# OttoPi06a-RPi3AHAT.net
KiCad netlist of a schematic drawn in EAGLE
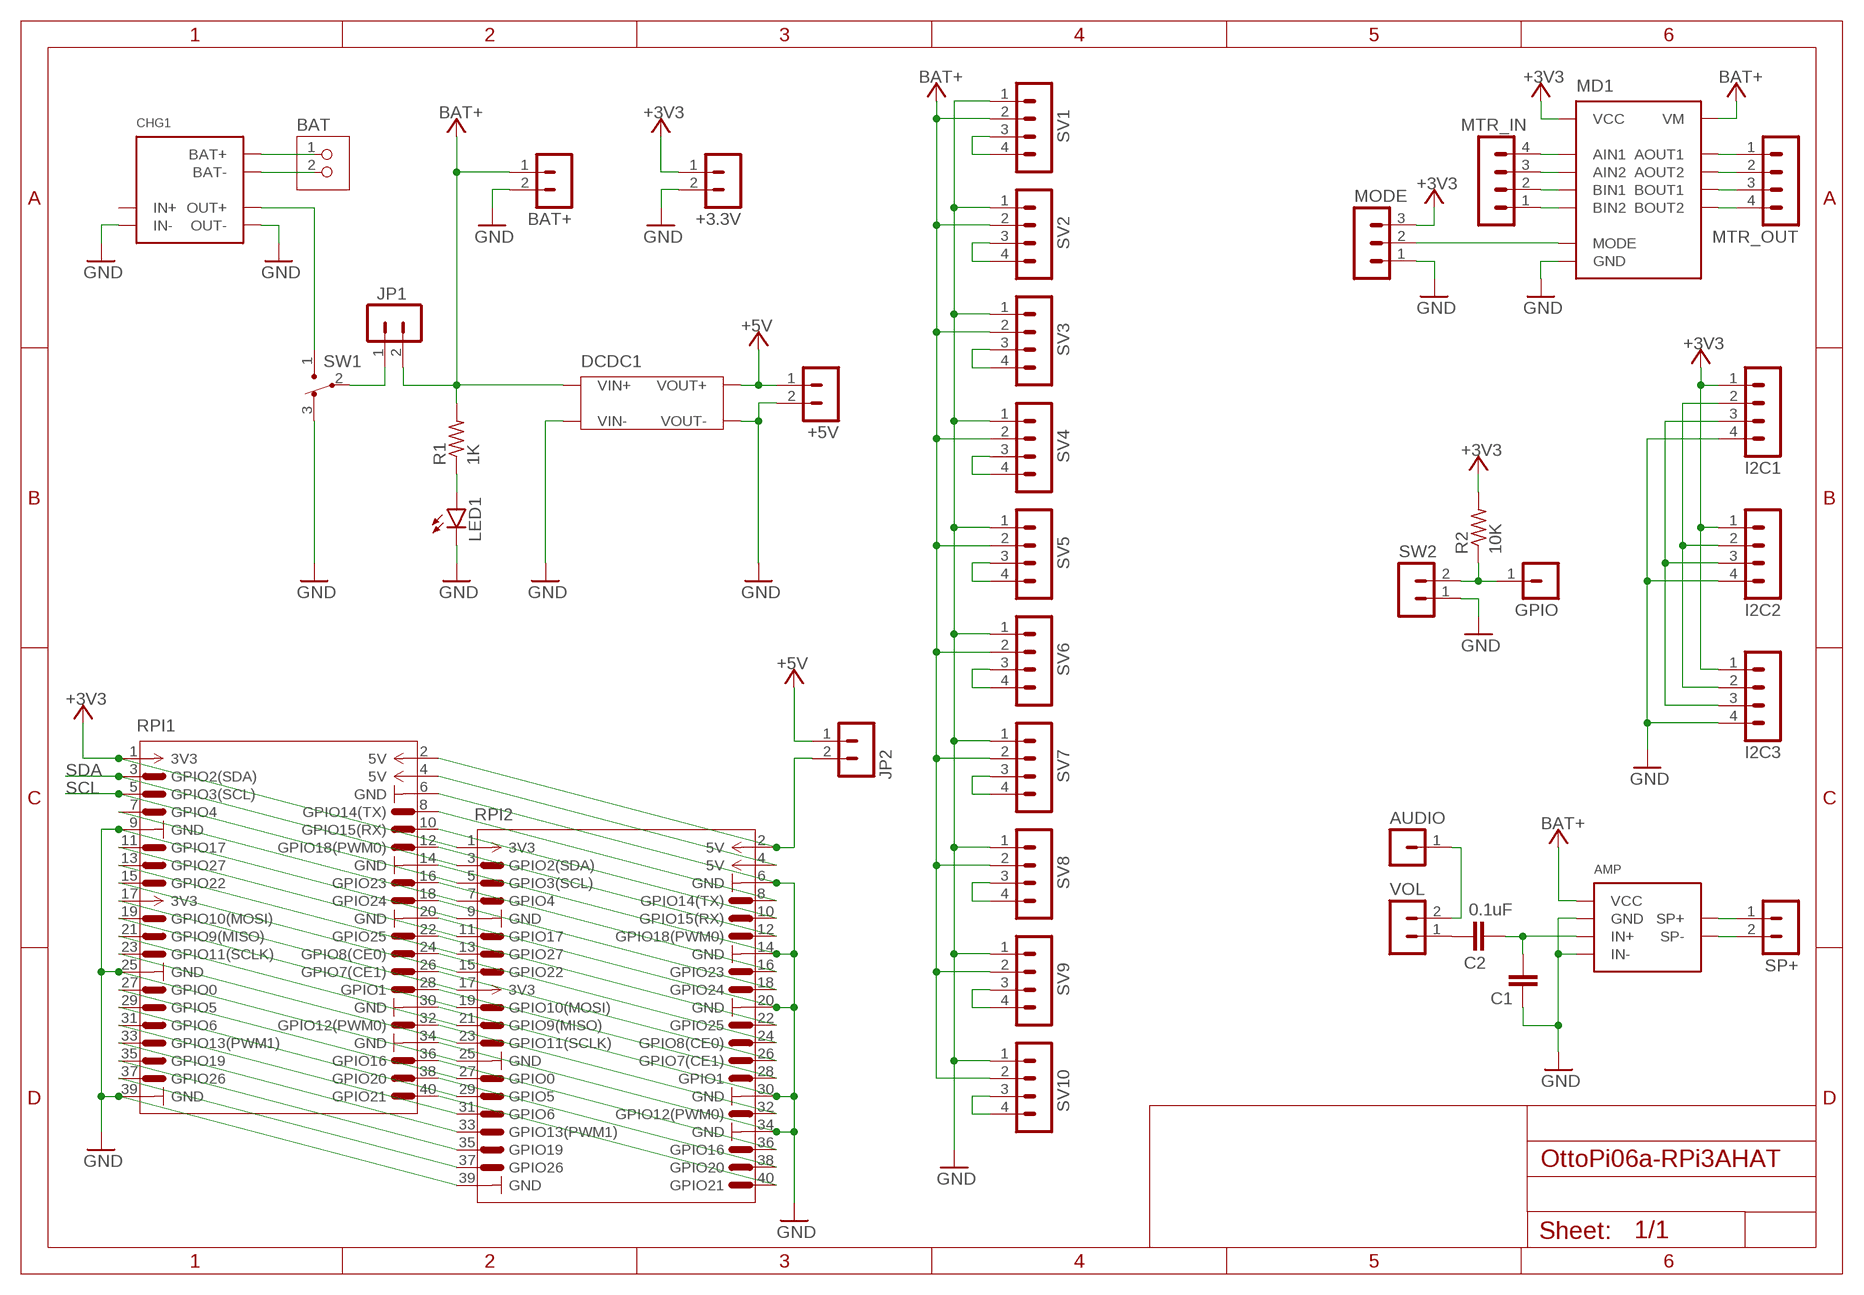
[diagram p0: schematic, sheet 1]

(export (version "E")
  (design (tool "Eeschema 10.0.6"))
  (components
    (comp (ref "+3.3V")
      (value "PINHEAD-MA02-1")
      (footprint "eagle-import:PINHEAD-MA02-1")
      (libsource (lib "eagle-import") (part "PINHEAD-MA02-1"))
    )
    (comp (ref "+5V")
      (value "PINHEAD-MA02-1")
      (footprint "eagle-import:PINHEAD-MA02-1")
      (libsource (lib "eagle-import") (part "PINHEAD-MA02-1"))
    )
    (comp (ref "AMP")
      (value "PAM8012MOD")
      (footprint "eagle-import:PAM8012MOD-A")
      (libsource (lib "eagle-import") (part "PAM8012MOD"))
    )
    (comp (ref "AUDIO")
      (value "PINHEAD-MA01-1")
      (footprint "eagle-import:PINHEAD-MA01-1")
      (libsource (lib "eagle-import") (part "PINHEAD-MA01-1"))
    )
    (comp (ref "BAT")
      (value "JST-PH2")
      (footprint "eagle-import:JST-PH2")
      (libsource (lib "eagle-import") (part "JST-PH2"))
    )
    (comp (ref "BAT+")
      (value "PINHEAD-MA02-1")
      (footprint "eagle-import:PINHEAD-MA02-1")
      (libsource (lib "eagle-import") (part "PINHEAD-MA02-1"))
    )
    (comp (ref "C1")
      (value "C-EU025-024X044")
      (footprint "eagle-import:C025-024X044")
      (libsource (lib "eagle-import") (part "C-EU025-024X044"))
    )
    (comp (ref "C2")
      (value "0.1uF")
      (footprint "eagle-import:C025-024X044")
      (libsource (lib "eagle-import") (part "C-EU025-024X044"))
    )
    (comp (ref "CHG1")
      (value "TP4056MOD1")
      (footprint "eagle-import:TP4056MOD1")
      (libsource (lib "eagle-import") (part "TP4056MOD1"))
    )
    (comp (ref "DCDC1")
      (value "DCDC-MT3608-MODUSB")
      (footprint "eagle-import:DCDC-MT3608-MOD2-USB")
      (libsource (lib "eagle-import") (part "DCDC-MT3608-MODUSB"))
    )
    (comp (ref "GPIO")
      (value "PINHEAD-MA01-1")
      (footprint "eagle-import:PINHEAD-MA01-1")
      (libsource (lib "eagle-import") (part "PINHEAD-MA01-1"))
    )
    (comp (ref "I2C1")
      (value "PINHEAD-MA04-1")
      (footprint "eagle-import:PINHEAD-MA04-1")
      (libsource (lib "eagle-import") (part "PINHEAD-MA04-1"))
    )
    (comp (ref "I2C2")
      (value "PINHEAD-MA04-1")
      (footprint "eagle-import:PINHEAD-MA04-1")
      (libsource (lib "eagle-import") (part "PINHEAD-MA04-1"))
    )
    (comp (ref "I2C3")
      (value "PINHEAD-MA04-1")
      (footprint "eagle-import:PINHEAD-MA04-1")
      (libsource (lib "eagle-import") (part "PINHEAD-MA04-1"))
    )
    (comp (ref "JP1")
      (value "PINHEAD-MA02-1")
      (footprint "eagle-import:PINHEAD-MA02-1")
      (libsource (lib "eagle-import") (part "PINHEAD-MA02-1"))
    )
    (comp (ref "JP2")
      (value "PINHEAD-MA02-1")
      (footprint "eagle-import:PINHEAD-MA02-1")
      (libsource (lib "eagle-import") (part "PINHEAD-MA02-1"))
    )
    (comp (ref "LED1")
      (value "LED3MM")
      (footprint "eagle-import:LED3MM")
      (libsource (lib "eagle-import") (part "LED3MM"))
    )
    (comp (ref "MD1")
      (value "DRV8835MOD")
      (footprint "eagle-import:DRV8835MOD")
      (libsource (lib "eagle-import") (part "DRV8835MOD"))
    )
    (comp (ref "MODE")
      (value "PINHEAD-MA03-1")
      (footprint "eagle-import:PINHEAD-MA03-1")
      (libsource (lib "eagle-import") (part "PINHEAD-MA03-1"))
    )
    (comp (ref "MTR_IN")
      (value "PINHEAD-MA04-1")
      (footprint "eagle-import:PINHEAD-MA04-1")
      (libsource (lib "eagle-import") (part "PINHEAD-MA04-1"))
    )
    (comp (ref "MTR_OUT")
      (value "PINHEAD-MA04-1")
      (footprint "eagle-import:PINHEAD-MA04-1")
      (libsource (lib "eagle-import") (part "PINHEAD-MA04-1"))
    )
    (comp (ref "R1")
      (value "1K")
      (footprint "eagle-import:0204_7")
      (libsource (lib "eagle-import") (part "R-US_0204/7"))
    )
    (comp (ref "R2")
      (value "10K")
      (footprint "eagle-import:0204_7")
      (libsource (lib "eagle-import") (part "R-US_0204/7"))
    )
    (comp (ref "RPI1")
      (value "RPI-PIN")
      (footprint "eagle-import:RPI-PIN")
      (libsource (lib "eagle-import") (part "RPI-PIN"))
    )
    (comp (ref "RPI2")
      (value "RPI-PIN")
      (footprint "eagle-import:RPI-PIN")
      (libsource (lib "eagle-import") (part "RPI-PIN"))
    )
    (comp (ref "SP+")
      (value "PINHEAD-MA02-1")
      (footprint "eagle-import:PINHEAD-MA02-1")
      (libsource (lib "eagle-import") (part "PINHEAD-MA02-1"))
    )
    (comp (ref "SV1")
      (value "PINHEAD-MA04-1")
      (footprint "eagle-import:PINHEAD-MA04-1")
      (libsource (lib "eagle-import") (part "PINHEAD-MA04-1"))
    )
    (comp (ref "SV2")
      (value "PINHEAD-MA04-1")
      (footprint "eagle-import:PINHEAD-MA04-1")
      (libsource (lib "eagle-import") (part "PINHEAD-MA04-1"))
    )
    (comp (ref "SV3")
      (value "PINHEAD-MA04-1")
      (footprint "eagle-import:PINHEAD-MA04-1")
      (libsource (lib "eagle-import") (part "PINHEAD-MA04-1"))
    )
    (comp (ref "SV4")
      (value "PINHEAD-MA04-1")
      (footprint "eagle-import:PINHEAD-MA04-1")
      (libsource (lib "eagle-import") (part "PINHEAD-MA04-1"))
    )
    (comp (ref "SV5")
      (value "PINHEAD-MA04-1")
      (footprint "eagle-import:PINHEAD-MA04-1")
      (libsource (lib "eagle-import") (part "PINHEAD-MA04-1"))
    )
    (comp (ref "SV6")
      (value "PINHEAD-MA04-1")
      (footprint "eagle-import:PINHEAD-MA04-1")
      (libsource (lib "eagle-import") (part "PINHEAD-MA04-1"))
    )
    (comp (ref "SV7")
      (value "PINHEAD-MA04-1")
      (footprint "eagle-import:PINHEAD-MA04-1")
      (libsource (lib "eagle-import") (part "PINHEAD-MA04-1"))
    )
    (comp (ref "SV8")
      (value "PINHEAD-MA04-1")
      (footprint "eagle-import:PINHEAD-MA04-1")
      (libsource (lib "eagle-import") (part "PINHEAD-MA04-1"))
    )
    (comp (ref "SV9")
      (value "PINHEAD-MA04-1")
      (footprint "eagle-import:PINHEAD-MA04-1")
      (libsource (lib "eagle-import") (part "PINHEAD-MA04-1"))
    )
    (comp (ref "SV10")
      (value "PINHEAD-MA04-1")
      (footprint "eagle-import:PINHEAD-MA04-1")
      (libsource (lib "eagle-import") (part "PINHEAD-MA04-1"))
    )
    (comp (ref "SW1")
      (value "SW3-1")
      (footprint "eagle-import:SW3-1")
      (fields (field (name "MF") "HiLetgo"))
      (libsource (lib "eagle-import") (part "SW3-1"))
    )
    (comp (ref "SW2")
      (value "PINHEAD-MA02-1")
      (footprint "eagle-import:PINHEAD-MA02-1")
      (libsource (lib "eagle-import") (part "PINHEAD-MA02-1"))
    )
    (comp (ref "VOL")
      (value "PINHEAD-MA02-1")
      (footprint "eagle-import:PINHEAD-MA02-1")
      (libsource (lib "eagle-import") (part "PINHEAD-MA02-1"))
    )
  )
  (nets
    (net (code "1") (name "+3V3") (class "Default")
      (node (ref "+3.3V") (pin "1") (pinfunction "1_1") (pintype "passive"))
      (node (ref "I2C1") (pin "1") (pinfunction "1_1") (pintype "passive"))
      (node (ref "I2C2") (pin "1") (pinfunction "1_1") (pintype "passive"))
      (node (ref "I2C3") (pin "1") (pinfunction "1_1") (pintype "passive"))
      (node (ref "MD1") (pin "VCC") (pinfunction "VCC_VCC") (pintype "input"))
      (node (ref "MODE") (pin "3") (pinfunction "3_3") (pintype "passive"))
      (node (ref "R2") (pin "2") (pinfunction "2_2") (pintype "passive"))
      (node (ref "RPI1") (pin "1") (pinfunction "3V3_1") (pintype "passive"))
      (node (ref "RPI2") (pin "1") (pinfunction "3V3_1") (pintype "passive"))
    )
    (net (code "2") (name "+5V") (class "Default")
      (node (ref "+5V") (pin "1") (pinfunction "1_1") (pintype "passive"))
      (node (ref "DCDC1") (pin "VOUT+") (pinfunction "VOUT+_VOUT+") (pintype "power_in"))
      (node (ref "JP2") (pin "1") (pinfunction "1_1") (pintype "passive"))
    )
    (net (code "3") (name "/SCL") (class "Default")
      (node (ref "I2C1") (pin "3") (pinfunction "3_3") (pintype "passive"))
      (node (ref "I2C2") (pin "3") (pinfunction "3_3") (pintype "passive"))
      (node (ref "I2C3") (pin "3") (pinfunction "3_3") (pintype "passive"))
      (node (ref "RPI1") (pin "5") (pinfunction "GPIO3(SCL)_5") (pintype "passive"))
      (node (ref "RPI2") (pin "5") (pinfunction "GPIO3(SCL)_5") (pintype "passive"))
    )
    (net (code "4") (name "/SDA") (class "Default")
      (node (ref "I2C1") (pin "2") (pinfunction "2_2") (pintype "passive"))
      (node (ref "I2C2") (pin "2") (pinfunction "2_2") (pintype "passive"))
      (node (ref "I2C3") (pin "2") (pinfunction "2_2") (pintype "passive"))
      (node (ref "RPI1") (pin "3") (pinfunction "GPIO2(SDA)_3") (pintype "passive"))
      (node (ref "RPI2") (pin "3") (pinfunction "GPIO2(SDA)_3") (pintype "passive"))
    )
    (net (code "5") (name "BAT+") (class "Default")
      (node (ref "AMP") (pin "V+") (pinfunction "VCC_V+") (pintype "passive"))
      (node (ref "BAT+") (pin "1") (pinfunction "1_1") (pintype "passive"))
      (node (ref "DCDC1") (pin "VIN+") (pinfunction "VIN+_VIN+") (pintype "power_in"))
      (node (ref "JP1") (pin "2") (pinfunction "2_2") (pintype "passive"))
      (node (ref "MD1") (pin "VM") (pinfunction "VM_VM") (pintype "input"))
      (node (ref "R1") (pin "2") (pinfunction "2_2") (pintype "passive"))
      (node (ref "SV1") (pin "2") (pinfunction "2_2") (pintype "passive"))
      (node (ref "SV10") (pin "2") (pinfunction "2_2") (pintype "passive"))
      (node (ref "SV2") (pin "2") (pinfunction "2_2") (pintype "passive"))
      (node (ref "SV3") (pin "2") (pinfunction "2_2") (pintype "passive"))
      (node (ref "SV4") (pin "2") (pinfunction "2_2") (pintype "passive"))
      (node (ref "SV5") (pin "2") (pinfunction "2_2") (pintype "passive"))
      (node (ref "SV6") (pin "2") (pinfunction "2_2") (pintype "passive"))
      (node (ref "SV7") (pin "2") (pinfunction "2_2") (pintype "passive"))
      (node (ref "SV8") (pin "2") (pinfunction "2_2") (pintype "passive"))
      (node (ref "SV9") (pin "2") (pinfunction "2_2") (pintype "passive"))
    )
    (net (code "6") (name "GND") (class "Default")
      (node (ref "+3.3V") (pin "2") (pinfunction "2_2") (pintype "passive"))
      (node (ref "+5V") (pin "2") (pinfunction "2_2") (pintype "passive"))
      (node (ref "AMP") (pin "GND") (pinfunction "GND_GND") (pintype "passive"))
      (node (ref "AMP") (pin "IN-") (pinfunction "IN-_IN-") (pintype "input"))
      (node (ref "BAT+") (pin "2") (pinfunction "2_2") (pintype "passive"))
      (node (ref "C1") (pin "1") (pinfunction "1_1") (pintype "passive"))
      (node (ref "CHG1") (pin "IN-") (pinfunction "IN-_IN-") (pintype "passive"))
      (node (ref "CHG1") (pin "OUT-") (pinfunction "OUT-_OUT-") (pintype "passive"))
      (node (ref "DCDC1") (pin "VIN-") (pinfunction "VIN-_VIN-") (pintype "power_in"))
      (node (ref "DCDC1") (pin "VOUT-") (pinfunction "VOUT-_VOUT-") (pintype "power_in"))
      (node (ref "I2C1") (pin "4") (pinfunction "4_4") (pintype "passive"))
      (node (ref "I2C2") (pin "4") (pinfunction "4_4") (pintype "passive"))
      (node (ref "I2C3") (pin "4") (pinfunction "4_4") (pintype "passive"))
      (node (ref "LED1") (pin "K") (pinfunction "C_K") (pintype "passive"))
      (node (ref "MD1") (pin "GND") (pinfunction "GND_GND") (pintype "power_in"))
      (node (ref "MODE") (pin "1") (pinfunction "1_1") (pintype "passive"))
      (node (ref "RPI1") (pin "14") (pinfunction "GND_14") (pintype "passive"))
      (node (ref "RPI1") (pin "20") (pinfunction "GND_20") (pintype "passive"))
      (node (ref "RPI1") (pin "25") (pinfunction "GND_25") (pintype "passive"))
      (node (ref "RPI1") (pin "30") (pinfunction "GND_30") (pintype "passive"))
      (node (ref "RPI1") (pin "34") (pinfunction "GND_34") (pintype "passive"))
      (node (ref "RPI1") (pin "39") (pinfunction "GND_39") (pintype "passive"))
      (node (ref "RPI1") (pin "6") (pinfunction "GND_6") (pintype "passive"))
      (node (ref "RPI1") (pin "9") (pinfunction "GND_9") (pintype "passive"))
      (node (ref "RPI2") (pin "14") (pinfunction "GND_14") (pintype "passive"))
      (node (ref "RPI2") (pin "20") (pinfunction "GND_20") (pintype "passive"))
      (node (ref "RPI2") (pin "25") (pinfunction "GND_25") (pintype "passive"))
      (node (ref "RPI2") (pin "30") (pinfunction "GND_30") (pintype "passive"))
      (node (ref "RPI2") (pin "34") (pinfunction "GND_34") (pintype "passive"))
      (node (ref "RPI2") (pin "39") (pinfunction "GND_39") (pintype "passive"))
      (node (ref "RPI2") (pin "6") (pinfunction "GND_6") (pintype "passive"))
      (node (ref "RPI2") (pin "9") (pinfunction "GND_9") (pintype "passive"))
      (node (ref "SV1") (pin "1") (pinfunction "1_1") (pintype "passive"))
      (node (ref "SV10") (pin "1") (pinfunction "1_1") (pintype "passive"))
      (node (ref "SV2") (pin "1") (pinfunction "1_1") (pintype "passive"))
      (node (ref "SV3") (pin "1") (pinfunction "1_1") (pintype "passive"))
      (node (ref "SV4") (pin "1") (pinfunction "1_1") (pintype "passive"))
      (node (ref "SV5") (pin "1") (pinfunction "1_1") (pintype "passive"))
      (node (ref "SV6") (pin "1") (pinfunction "1_1") (pintype "passive"))
      (node (ref "SV7") (pin "1") (pinfunction "1_1") (pintype "passive"))
      (node (ref "SV8") (pin "1") (pinfunction "1_1") (pintype "passive"))
      (node (ref "SV9") (pin "1") (pinfunction "1_1") (pintype "passive"))
      (node (ref "SW1") (pin "3") (pinfunction "3_3") (pintype "passive"))
      (node (ref "SW2") (pin "1") (pinfunction "1_1") (pintype "passive"))
    )
    (net (code "7") (name "Net-(AMP-PadIN+)") (class "Default")
      (node (ref "AMP") (pin "IN+") (pinfunction "IN+_IN+") (pintype "input"))
      (node (ref "C1") (pin "2") (pinfunction "2_2") (pintype "passive"))
      (node (ref "C2") (pin "1") (pinfunction "1_1") (pintype "passive"))
    )
    (net (code "8") (name "Net-(AMP-SP+)") (class "Default")
      (node (ref "AMP") (pin "SP+@1") (pinfunction "SP+_SP+@1") (pintype "output"))
      (node (ref "SP+") (pin "1") (pinfunction "1_1") (pintype "passive"))
    )
    (net (code "9") (name "Net-(AMP-SP-)") (class "Default")
      (node (ref "AMP") (pin "SP-@1") (pinfunction "SP-_SP-@1") (pintype "output"))
      (node (ref "SP+") (pin "2") (pinfunction "2_2") (pintype "passive"))
    )
    (net (code "10") (name "Net-(AUDIO-Pad1)") (class "Default")
      (node (ref "AUDIO") (pin "1") (pinfunction "1_1") (pintype "passive"))
      (node (ref "VOL") (pin "2") (pinfunction "2_2") (pintype "passive"))
    )
    (net (code "11") (name "Net-(BAT-Pad1)") (class "Default")
      (node (ref "BAT") (pin "1") (pinfunction "1_1") (pintype "passive"))
      (node (ref "CHG1") (pin "BAT+") (pinfunction "BAT+_BAT+") (pintype "passive"))
    )
    (net (code "12") (name "Net-(BAT-Pad2)") (class "Default")
      (node (ref "BAT") (pin "2") (pinfunction "2_2") (pintype "passive"))
      (node (ref "CHG1") (pin "BAT-") (pinfunction "BAT-_BAT-") (pintype "passive"))
    )
    (net (code "13") (name "Net-(C2-Pad2)") (class "Default")
      (node (ref "C2") (pin "2") (pinfunction "2_2") (pintype "passive"))
      (node (ref "VOL") (pin "1") (pinfunction "1_1") (pintype "passive"))
    )
    (net (code "14") (name "Net-(CHG1-PadOUT+)") (class "Default")
      (node (ref "CHG1") (pin "OUT+") (pinfunction "OUT+_OUT+") (pintype "passive"))
      (node (ref "SW1") (pin "1") (pinfunction "1_1") (pintype "passive"))
    )
    (net (code "15") (name "Net-(GPIO-Pad1)") (class "Default")
      (node (ref "GPIO") (pin "1") (pinfunction "1_1") (pintype "passive"))
      (node (ref "R2") (pin "1") (pinfunction "1_1") (pintype "passive"))
      (node (ref "SW2") (pin "2") (pinfunction "2_2") (pintype "passive"))
    )
    (net (code "16") (name "Net-(JP1-Pad1)") (class "Default")
      (node (ref "JP1") (pin "1") (pinfunction "1_1") (pintype "passive"))
      (node (ref "SW1") (pin "2") (pinfunction "2_2") (pintype "passive"))
    )
    (net (code "17") (name "Net-(JP2-Pad2)") (class "Default")
      (node (ref "JP2") (pin "2") (pinfunction "2_2") (pintype "passive"))
      (node (ref "RPI1") (pin "2") (pinfunction "5V_2") (pintype "passive"))
      (node (ref "RPI2") (pin "2") (pinfunction "5V_2") (pintype "passive"))
    )
    (net (code "18") (name "Net-(LED1-PadA)") (class "Default")
      (node (ref "LED1") (pin "A") (pinfunction "A_A") (pintype "passive"))
      (node (ref "R1") (pin "1") (pinfunction "1_1") (pintype "passive"))
    )
    (net (code "19") (name "Net-(MD1-PadAIN1)") (class "Default")
      (node (ref "MD1") (pin "AIN1") (pinfunction "AIN1_AIN1") (pintype "input"))
      (node (ref "MTR_IN") (pin "4") (pinfunction "4_4") (pintype "passive"))
    )
    (net (code "20") (name "Net-(MD1-PadAIN2)") (class "Default")
      (node (ref "MD1") (pin "AIN2") (pinfunction "AIN2_AIN2") (pintype "input"))
      (node (ref "MTR_IN") (pin "3") (pinfunction "3_3") (pintype "passive"))
    )
    (net (code "21") (name "Net-(MD1-PadAOUT1)") (class "Default")
      (node (ref "MD1") (pin "AOUT1") (pinfunction "AOUT1_AOUT1") (pintype "output"))
      (node (ref "MTR_OUT") (pin "1") (pinfunction "1_1") (pintype "passive"))
    )
    (net (code "22") (name "Net-(MD1-PadAOUT2)") (class "Default")
      (node (ref "MD1") (pin "AOUT2") (pinfunction "AOUT2_AOUT2") (pintype "output"))
      (node (ref "MTR_OUT") (pin "2") (pinfunction "2_2") (pintype "passive"))
    )
    (net (code "23") (name "Net-(MD1-PadBIN1)") (class "Default")
      (node (ref "MD1") (pin "BIN1") (pinfunction "BIN1_BIN1") (pintype "input"))
      (node (ref "MTR_IN") (pin "2") (pinfunction "2_2") (pintype "passive"))
    )
    (net (code "24") (name "Net-(MD1-PadBIN2)") (class "Default")
      (node (ref "MD1") (pin "BIN2") (pinfunction "BIN2_BIN2") (pintype "input"))
      (node (ref "MTR_IN") (pin "1") (pinfunction "1_1") (pintype "passive"))
    )
    (net (code "25") (name "Net-(MD1-PadBOUT1)") (class "Default")
      (node (ref "MD1") (pin "BOUT1") (pinfunction "BOUT1_BOUT1") (pintype "output"))
      (node (ref "MTR_OUT") (pin "3") (pinfunction "3_3") (pintype "passive"))
    )
    (net (code "26") (name "Net-(MD1-PadBOUT2)") (class "Default")
      (node (ref "MD1") (pin "BOUT2") (pinfunction "BOUT2_BOUT2") (pintype "output"))
      (node (ref "MTR_OUT") (pin "4") (pinfunction "4_4") (pintype "passive"))
    )
    (net (code "27") (name "Net-(MD1-PadMODE)") (class "Default")
      (node (ref "MD1") (pin "MODE") (pinfunction "MODE_MODE") (pintype "input"))
      (node (ref "MODE") (pin "2") (pinfunction "2_2") (pintype "passive"))
    )
    (net (code "28") (name "Net-(RPI1-3V3-Pad17)") (class "Default")
      (node (ref "RPI1") (pin "17") (pinfunction "3V3_17") (pintype "passive"))
      (node (ref "RPI2") (pin "17") (pinfunction "3V3_17") (pintype "passive"))
    )
    (net (code "29") (name "Net-(RPI1-5V-Pad4)") (class "Default")
      (node (ref "RPI1") (pin "4") (pinfunction "5V_4") (pintype "passive"))
      (node (ref "RPI2") (pin "4") (pinfunction "5V_4") (pintype "passive"))
    )
    (net (code "30") (name "Net-(RPI1-GPIO0)") (class "Default")
      (node (ref "RPI1") (pin "27") (pinfunction "GPIO0_27") (pintype "passive"))
      (node (ref "RPI2") (pin "27") (pinfunction "GPIO0_27") (pintype "passive"))
    )
    (net (code "31") (name "Net-(RPI1-GPIO1)") (class "Default")
      (node (ref "RPI1") (pin "28") (pinfunction "GPIO1_28") (pintype "passive"))
      (node (ref "RPI2") (pin "28") (pinfunction "GPIO1_28") (pintype "passive"))
    )
    (net (code "32") (name "Net-(RPI1-GPIO4)") (class "Default")
      (node (ref "RPI1") (pin "7") (pinfunction "GPIO4_7") (pintype "passive"))
      (node (ref "RPI2") (pin "7") (pinfunction "GPIO4_7") (pintype "passive"))
    )
    (net (code "33") (name "Net-(RPI1-GPIO5)") (class "Default")
      (node (ref "RPI1") (pin "29") (pinfunction "GPIO5_29") (pintype "passive"))
      (node (ref "RPI2") (pin "29") (pinfunction "GPIO5_29") (pintype "passive"))
    )
    (net (code "34") (name "Net-(RPI1-GPIO6)") (class "Default")
      (node (ref "RPI1") (pin "31") (pinfunction "GPIO6_31") (pintype "passive"))
      (node (ref "RPI2") (pin "31") (pinfunction "GPIO6_31") (pintype "passive"))
    )
    (net (code "35") (name "Net-(RPI1-GPIO7(CE1))") (class "Default")
      (node (ref "RPI1") (pin "26") (pinfunction "GPIO7(CE1)_26") (pintype "passive"))
      (node (ref "RPI2") (pin "26") (pinfunction "GPIO7(CE1)_26") (pintype "passive"))
    )
    (net (code "36") (name "Net-(RPI1-GPIO8(CE0))") (class "Default")
      (node (ref "RPI1") (pin "24") (pinfunction "GPIO8(CE0)_24") (pintype "passive"))
      (node (ref "RPI2") (pin "24") (pinfunction "GPIO8(CE0)_24") (pintype "passive"))
    )
    (net (code "37") (name "Net-(RPI1-GPIO9(MISO))") (class "Default")
      (node (ref "RPI1") (pin "21") (pinfunction "GPIO9(MISO)_21") (pintype "passive"))
      (node (ref "RPI2") (pin "21") (pinfunction "GPIO9(MISO)_21") (pintype "passive"))
    )
    (net (code "38") (name "Net-(RPI1-GPIO10(MOSI))") (class "Default")
      (node (ref "RPI1") (pin "19") (pinfunction "GPIO10(MOSI)_19") (pintype "passive"))
      (node (ref "RPI2") (pin "19") (pinfunction "GPIO10(MOSI)_19") (pintype "passive"))
    )
    (net (code "39") (name "Net-(RPI1-GPIO11(SCLK))") (class "Default")
      (node (ref "RPI1") (pin "23") (pinfunction "GPIO11(SCLK)_23") (pintype "passive"))
      (node (ref "RPI2") (pin "23") (pinfunction "GPIO11(SCLK)_23") (pintype "passive"))
    )
    (net (code "40") (name "Net-(RPI1-GPIO12(PWM0))") (class "Default")
      (node (ref "RPI1") (pin "32") (pinfunction "GPIO12(PWM0)_32") (pintype "passive"))
      (node (ref "RPI2") (pin "32") (pinfunction "GPIO12(PWM0)_32") (pintype "passive"))
    )
    (net (code "41") (name "Net-(RPI1-GPIO13(PWM1))") (class "Default")
      (node (ref "RPI1") (pin "33") (pinfunction "GPIO13(PWM1)_33") (pintype "passive"))
      (node (ref "RPI2") (pin "33") (pinfunction "GPIO13(PWM1)_33") (pintype "passive"))
    )
    (net (code "42") (name "Net-(RPI1-GPIO14(TX))") (class "Default")
      (node (ref "RPI1") (pin "8") (pinfunction "GPIO14(TX)_8") (pintype "passive"))
      (node (ref "RPI2") (pin "8") (pinfunction "GPIO14(TX)_8") (pintype "passive"))
    )
    (net (code "43") (name "Net-(RPI1-GPIO15(RX))") (class "Default")
      (node (ref "RPI1") (pin "10") (pinfunction "GPIO15(RX)_10") (pintype "passive"))
      (node (ref "RPI2") (pin "10") (pinfunction "GPIO15(RX)_10") (pintype "passive"))
    )
    (net (code "44") (name "Net-(RPI1-GPIO16)") (class "Default")
      (node (ref "RPI1") (pin "36") (pinfunction "GPIO16_36") (pintype "passive"))
      (node (ref "RPI2") (pin "36") (pinfunction "GPIO16_36") (pintype "passive"))
    )
    (net (code "45") (name "Net-(RPI1-GPIO17)") (class "Default")
      (node (ref "RPI1") (pin "11") (pinfunction "GPIO17_11") (pintype "passive"))
      (node (ref "RPI2") (pin "11") (pinfunction "GPIO17_11") (pintype "passive"))
    )
    (net (code "46") (name "Net-(RPI1-GPIO18(PWM0))") (class "Default")
      (node (ref "RPI1") (pin "12") (pinfunction "GPIO18(PWM0)_12") (pintype "passive"))
      (node (ref "RPI2") (pin "12") (pinfunction "GPIO18(PWM0)_12") (pintype "passive"))
    )
    (net (code "47") (name "Net-(RPI1-GPIO19)") (class "Default")
      (node (ref "RPI1") (pin "35") (pinfunction "GPIO19_35") (pintype "passive"))
      (node (ref "RPI2") (pin "35") (pinfunction "GPIO19_35") (pintype "passive"))
    )
    (net (code "48") (name "Net-(RPI1-GPIO20)") (class "Default")
      (node (ref "RPI1") (pin "38") (pinfunction "GPIO20_38") (pintype "passive"))
      (node (ref "RPI2") (pin "38") (pinfunction "GPIO20_38") (pintype "passive"))
    )
    (net (code "49") (name "Net-(RPI1-GPIO21)") (class "Default")
      (node (ref "RPI1") (pin "40") (pinfunction "GPIO21_40") (pintype "passive"))
      (node (ref "RPI2") (pin "40") (pinfunction "GPIO21_40") (pintype "passive"))
    )
    (net (code "50") (name "Net-(RPI1-GPIO22)") (class "Default")
      (node (ref "RPI1") (pin "15") (pinfunction "GPIO22_15") (pintype "passive"))
      (node (ref "RPI2") (pin "15") (pinfunction "GPIO22_15") (pintype "passive"))
    )
    (net (code "51") (name "Net-(RPI1-GPIO23)") (class "Default")
      (node (ref "RPI1") (pin "16") (pinfunction "GPIO23_16") (pintype "passive"))
      (node (ref "RPI2") (pin "16") (pinfunction "GPIO23_16") (pintype "passive"))
    )
    (net (code "52") (name "Net-(RPI1-GPIO24)") (class "Default")
      (node (ref "RPI1") (pin "18") (pinfunction "GPIO24_18") (pintype "passive"))
      (node (ref "RPI2") (pin "18") (pinfunction "GPIO24_18") (pintype "passive"))
    )
    (net (code "53") (name "Net-(RPI1-GPIO25)") (class "Default")
      (node (ref "RPI1") (pin "22") (pinfunction "GPIO25_22") (pintype "passive"))
      (node (ref "RPI2") (pin "22") (pinfunction "GPIO25_22") (pintype "passive"))
    )
    (net (code "54") (name "Net-(RPI1-GPIO26)") (class "Default")
      (node (ref "RPI1") (pin "37") (pinfunction "GPIO26_37") (pintype "passive"))
      (node (ref "RPI2") (pin "37") (pinfunction "GPIO26_37") (pintype "passive"))
    )
    (net (code "55") (name "Net-(RPI1-GPIO27)") (class "Default")
      (node (ref "RPI1") (pin "13") (pinfunction "GPIO27_13") (pintype "passive"))
      (node (ref "RPI2") (pin "13") (pinfunction "GPIO27_13") (pintype "passive"))
    )
    (net (code "56") (name "Net-(SV1-Pad3)") (class "Default")
      (node (ref "SV1") (pin "3") (pinfunction "3_3") (pintype "passive"))
      (node (ref "SV1") (pin "4") (pinfunction "4_4") (pintype "passive"))
    )
    (net (code "57") (name "Net-(SV2-Pad3)") (class "Default")
      (node (ref "SV2") (pin "3") (pinfunction "3_3") (pintype "passive"))
      (node (ref "SV2") (pin "4") (pinfunction "4_4") (pintype "passive"))
    )
    (net (code "58") (name "Net-(SV3-Pad3)") (class "Default")
      (node (ref "SV3") (pin "3") (pinfunction "3_3") (pintype "passive"))
      (node (ref "SV3") (pin "4") (pinfunction "4_4") (pintype "passive"))
    )
    (net (code "59") (name "Net-(SV4-Pad3)") (class "Default")
      (node (ref "SV4") (pin "3") (pinfunction "3_3") (pintype "passive"))
      (node (ref "SV4") (pin "4") (pinfunction "4_4") (pintype "passive"))
    )
    (net (code "60") (name "Net-(SV5-Pad3)") (class "Default")
      (node (ref "SV5") (pin "3") (pinfunction "3_3") (pintype "passive"))
      (node (ref "SV5") (pin "4") (pinfunction "4_4") (pintype "passive"))
    )
    (net (code "61") (name "Net-(SV6-Pad3)") (class "Default")
      (node (ref "SV6") (pin "3") (pinfunction "3_3") (pintype "passive"))
      (node (ref "SV6") (pin "4") (pinfunction "4_4") (pintype "passive"))
    )
    (net (code "62") (name "Net-(SV7-Pad3)") (class "Default")
      (node (ref "SV7") (pin "3") (pinfunction "3_3") (pintype "passive"))
      (node (ref "SV7") (pin "4") (pinfunction "4_4") (pintype "passive"))
    )
    (net (code "63") (name "Net-(SV8-Pad3)") (class "Default")
      (node (ref "SV8") (pin "3") (pinfunction "3_3") (pintype "passive"))
      (node (ref "SV8") (pin "4") (pinfunction "4_4") (pintype "passive"))
    )
    (net (code "64") (name "Net-(SV9-Pad3)") (class "Default")
      (node (ref "SV9") (pin "3") (pinfunction "3_3") (pintype "passive"))
      (node (ref "SV9") (pin "4") (pinfunction "4_4") (pintype "passive"))
    )
    (net (code "65") (name "Net-(SV10-Pad3)") (class "Default")
      (node (ref "SV10") (pin "3") (pinfunction "3_3") (pintype "passive"))
      (node (ref "SV10") (pin "4") (pinfunction "4_4") (pintype "passive"))
    )
    (net (code "66") (name "unconnected-(CHG1-PadIN+)") (class "Default")
      (node (ref "CHG1") (pin "IN+") (pinfunction "IN+_IN+") (pintype "passive"))
    )
  )
)
